# Power.net
KiCad netlist of a schematic drawn in Altium Designer
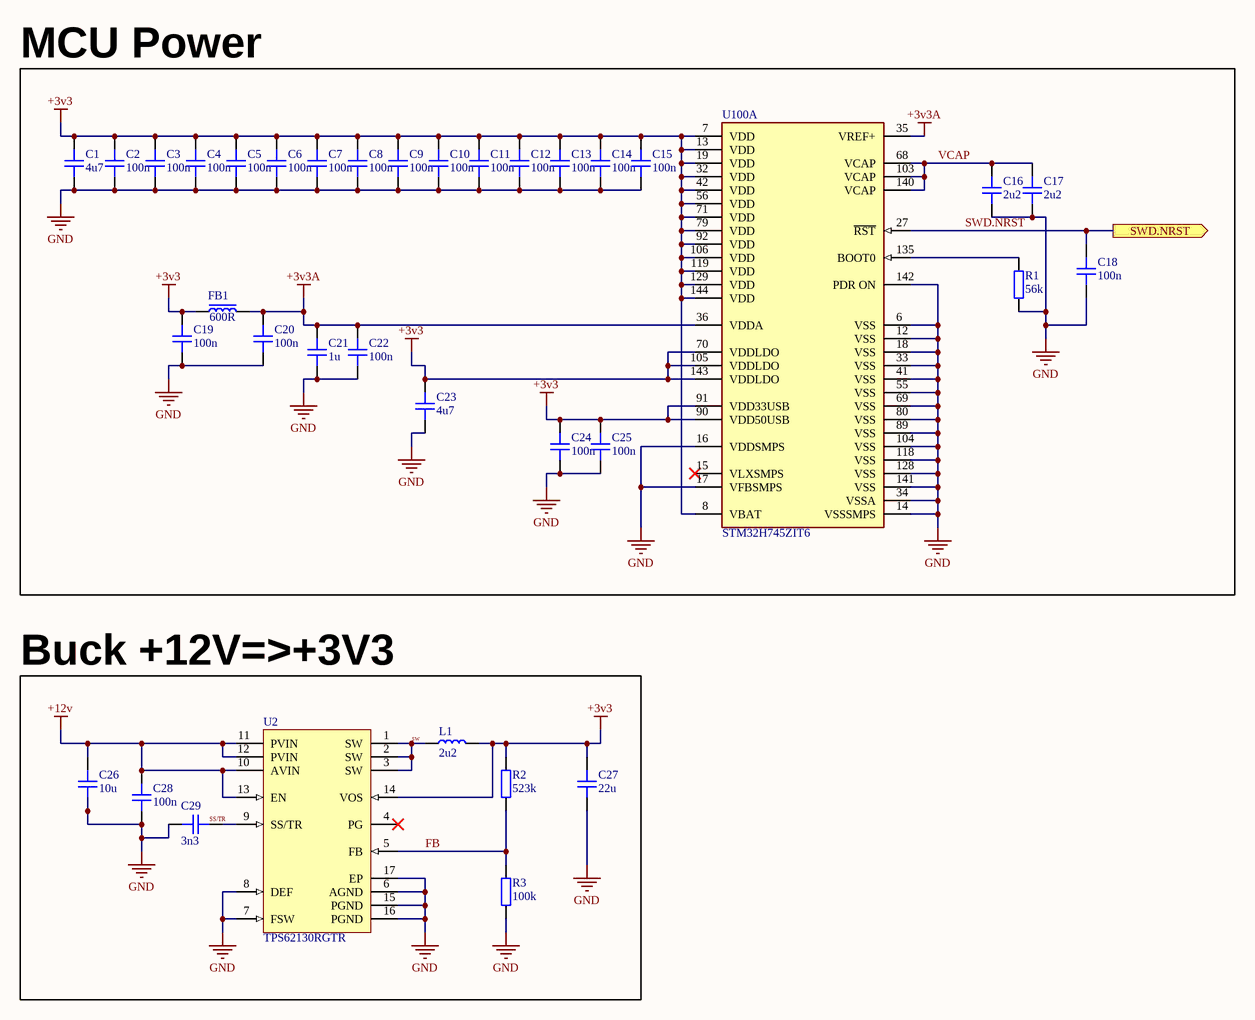
[diagram p0: Power.SchDoc]

(export (version "E")
  (design (tool "Eeschema 10.0.6"))
  (components
    (comp (ref "C1")
      (value "4u7")
      (footprint "CAP_0603")
      (description "Capacitor SMD 0603")
      (libsource (lib "Schematic-Lib-PhilsLab") (part "CAP_0603"))
    )
    (comp (ref "C2")
      (value "100n")
      (footprint "CAP_0402")
      (description "Capacitor SMD 0402")
      (libsource (lib "Schematic-Lib-PhilsLab") (part "CAP_0402"))
    )
    (comp (ref "C3")
      (value "100n")
      (footprint "CAP_0402")
      (description "Capacitor SMD 0402")
      (libsource (lib "Schematic-Lib-PhilsLab") (part "CAP_0402"))
    )
    (comp (ref "C4")
      (value "100n")
      (footprint "CAP_0402")
      (description "Capacitor SMD 0402")
      (libsource (lib "Schematic-Lib-PhilsLab") (part "CAP_0402"))
    )
    (comp (ref "C5")
      (value "100n")
      (footprint "CAP_0402")
      (description "Capacitor SMD 0402")
      (libsource (lib "Schematic-Lib-PhilsLab") (part "CAP_0402"))
    )
    (comp (ref "C6")
      (value "100n")
      (footprint "CAP_0402")
      (description "Capacitor SMD 0402")
      (libsource (lib "Schematic-Lib-PhilsLab") (part "CAP_0402"))
    )
    (comp (ref "C7")
      (value "100n")
      (footprint "CAP_0402")
      (description "Capacitor SMD 0402")
      (libsource (lib "Schematic-Lib-PhilsLab") (part "CAP_0402"))
    )
    (comp (ref "C8")
      (value "100n")
      (footprint "CAP_0402")
      (description "Capacitor SMD 0402")
      (libsource (lib "Schematic-Lib-PhilsLab") (part "CAP_0402"))
    )
    (comp (ref "C9")
      (value "100n")
      (footprint "CAP_0402")
      (description "Capacitor SMD 0402")
      (libsource (lib "Schematic-Lib-PhilsLab") (part "CAP_0402"))
    )
    (comp (ref "C10")
      (value "100n")
      (footprint "CAP_0402")
      (description "Capacitor SMD 0402")
      (libsource (lib "Schematic-Lib-PhilsLab") (part "CAP_0402"))
    )
    (comp (ref "C11")
      (value "100n")
      (footprint "CAP_0402")
      (description "Capacitor SMD 0402")
      (libsource (lib "Schematic-Lib-PhilsLab") (part "CAP_0402"))
    )
    (comp (ref "C12")
      (value "100n")
      (footprint "CAP_0402")
      (description "Capacitor SMD 0402")
      (libsource (lib "Schematic-Lib-PhilsLab") (part "CAP_0402"))
    )
    (comp (ref "C13")
      (value "100n")
      (footprint "CAP_0402")
      (description "Capacitor SMD 0402")
      (libsource (lib "Schematic-Lib-PhilsLab") (part "CAP_0402"))
    )
    (comp (ref "C14")
      (value "100n")
      (footprint "CAP_0402")
      (description "Capacitor SMD 0402")
      (libsource (lib "Schematic-Lib-PhilsLab") (part "CAP_0402"))
    )
    (comp (ref "C15")
      (value "100n")
      (footprint "CAP_0402")
      (description "Capacitor SMD 0402")
      (libsource (lib "Schematic-Lib-PhilsLab") (part "CAP_0402"))
    )
    (comp (ref "C16")
      (value "2u2")
      (footprint "CAP_0402")
      (description "Capacitor SMD 0402")
      (libsource (lib "Schematic-Lib-PhilsLab") (part "CAP_0402"))
    )
    (comp (ref "C17")
      (value "2u2")
      (footprint "CAP_0402")
      (description "Capacitor SMD 0402")
      (libsource (lib "Schematic-Lib-PhilsLab") (part "CAP_0402"))
    )
    (comp (ref "C18")
      (value "100n")
      (footprint "CAP_0402")
      (description "Capacitor SMD 0402")
      (libsource (lib "Schematic-Lib-PhilsLab") (part "CAP_0402"))
    )
    (comp (ref "C19")
      (value "100n")
      (footprint "CAP_0402")
      (description "Capacitor SMD 0402")
      (libsource (lib "Schematic-Lib-PhilsLab") (part "CAP_0402"))
    )
    (comp (ref "C20")
      (value "100n")
      (footprint "CAP_0402")
      (description "Capacitor SMD 0402")
      (libsource (lib "Schematic-Lib-PhilsLab") (part "CAP_0402"))
    )
    (comp (ref "C21")
      (value "1u")
      (footprint "CAP_0402")
      (description "Capacitor SMD 0402")
      (libsource (lib "Schematic-Lib-PhilsLab") (part "CAP_0402"))
    )
    (comp (ref "C22")
      (value "100n")
      (footprint "CAP_0402")
      (description "Capacitor SMD 0402")
      (libsource (lib "Schematic-Lib-PhilsLab") (part "CAP_0402"))
    )
    (comp (ref "C23")
      (value "4u7")
      (footprint "CAP_0603")
      (description "Capacitor SMD 0603")
      (libsource (lib "Schematic-Lib-PhilsLab") (part "CAP_0603"))
    )
    (comp (ref "C24")
      (value "100n")
      (footprint "CAP_0402")
      (description "Capacitor SMD 0402")
      (libsource (lib "Schematic-Lib-PhilsLab") (part "CAP_0402"))
    )
    (comp (ref "C25")
      (value "100n")
      (footprint "CAP_0402")
      (description "Capacitor SMD 0402")
      (libsource (lib "Schematic-Lib-PhilsLab") (part "CAP_0402"))
    )
    (comp (ref "C26")
      (value "10u")
      (footprint "CAP_0805")
      (description "Capacitor SMD 0805")
      (libsource (lib "Schematic-Lib-PhilsLab") (part "CAP_0805"))
    )
    (comp (ref "C27")
      (value "22u")
      (footprint "CAP_0805")
      (description "Capacitor SMD 0805")
      (libsource (lib "Schematic-Lib-PhilsLab") (part "CAP_0805"))
    )
    (comp (ref "C28")
      (value "100n")
      (footprint "CAP_0402")
      (description "Capacitor SMD 0402")
      (libsource (lib "Schematic-Lib-PhilsLab") (part "CAP_0402"))
    )
    (comp (ref "C29")
      (value "3n3")
      (footprint "CAP_0402")
      (description "Capacitor SMD 0402")
      (libsource (lib "Schematic-Lib-PhilsLab") (part "CAP_0402"))
    )
    (comp (ref "FB1")
      (value "600R")
      (footprint "FB_0603")
      (description "Ferrite Bead SMD 0603 2A 350mΩ 600Ω@100MHz ±25%")
      (libsource (lib "Schematic-Lib-PhilsLab") (part "FB_0603"))
    )
    (comp (ref "L1")
      (value "2u2")
      (footprint "IND_1008")
      (description "Inductor SMD 1008")
      (libsource (lib "Schematic-Lib-PhilsLab") (part "IND_1008"))
    )
    (comp (ref "R1")
      (value "56k")
      (footprint "RES_0402")
      (description "Resistor SMD 0402")
      (libsource (lib "Schematic-Lib-PhilsLab") (part "RES_0402"))
    )
    (comp (ref "R2")
      (value "523k")
      (footprint "RES_0402")
      (description "Resistor SMD 0402")
      (libsource (lib "Schematic-Lib-PhilsLab") (part "RES_0402"))
    )
    (comp (ref "R3")
      (value "100k")
      (footprint "RES_0402")
      (description "Resistor SMD 0402")
      (libsource (lib "Schematic-Lib-PhilsLab") (part "RES_0402"))
    )
    (comp (ref "U2")
      (value "TPS62130RGTR")
      (footprint "RGT0016C_V")
      (fields (field (name "MANUFACTURER") "Texas Instruments"))
      (libsource (lib "Altium Content Vault") (part "TI-TPS62130RGT16-1700X1700TP"))
    )
    (comp (ref "U100")
      (value "STM32H745ZIT6")
      (footprint "FP-LQFP144-1A-MFG")
      (description "HIGH-PERFORMANCE AND DSP WITH DP")
      (fields
        (field (name "OCTOPART") "https://octopart.com/stm32h745zit6-stmicroelectronics-100293939")
        (field (name "MANUFACTURER") "STMicroelectronics")
      )
      (libsource (lib "Altium Content Vault") (part "f5432ce9894f79c0085309acf87c031"))
    )
  )
  (nets
    (net (code "1") (name "+3v3") (class "Default")
      (node (ref "C1") (pin "2") (pinfunction "2_2") (pintype "passive"))
      (node (ref "C10") (pin "2") (pinfunction "2_2") (pintype "passive"))
      (node (ref "C11") (pin "2") (pinfunction "2_2") (pintype "passive"))
      (node (ref "C12") (pin "2") (pinfunction "2_2") (pintype "passive"))
      (node (ref "C13") (pin "2") (pinfunction "2_2") (pintype "passive"))
      (node (ref "C14") (pin "2") (pinfunction "2_2") (pintype "passive"))
      (node (ref "C15") (pin "2") (pinfunction "2_2") (pintype "passive"))
      (node (ref "C19") (pin "2") (pinfunction "2_2") (pintype "passive"))
      (node (ref "C2") (pin "2") (pinfunction "2_2") (pintype "passive"))
      (node (ref "C23") (pin "2") (pinfunction "2_2") (pintype "passive"))
      (node (ref "C24") (pin "2") (pinfunction "2_2") (pintype "passive"))
      (node (ref "C25") (pin "2") (pinfunction "2_2") (pintype "passive"))
      (node (ref "C27") (pin "2") (pinfunction "2_2") (pintype "passive"))
      (node (ref "C3") (pin "2") (pinfunction "2_2") (pintype "passive"))
      (node (ref "C4") (pin "2") (pinfunction "2_2") (pintype "passive"))
      (node (ref "C5") (pin "2") (pinfunction "2_2") (pintype "passive"))
      (node (ref "C6") (pin "2") (pinfunction "2_2") (pintype "passive"))
      (node (ref "C7") (pin "2") (pinfunction "2_2") (pintype "passive"))
      (node (ref "C8") (pin "2") (pinfunction "2_2") (pintype "passive"))
      (node (ref "C9") (pin "2") (pinfunction "2_2") (pintype "passive"))
      (node (ref "FB1") (pin "1") (pinfunction "1_1") (pintype "passive"))
      (node (ref "L1") (pin "2") (pinfunction "2_2") (pintype "passive"))
      (node (ref "R2") (pin "2") (pinfunction "2_2") (pintype "passive"))
      (node (ref "U100") (pin "105") (pinfunction "VDDLDO_105") (pintype "power_in"))
      (node (ref "U100") (pin "106") (pinfunction "VDD_106") (pintype "power_in"))
      (node (ref "U100") (pin "119") (pinfunction "VDD_119") (pintype "power_in"))
      (node (ref "U100") (pin "129") (pinfunction "VDD_129") (pintype "power_in"))
      (node (ref "U100") (pin "13") (pinfunction "VDD_13") (pintype "power_in"))
      (node (ref "U100") (pin "143") (pinfunction "VDDLDO_143") (pintype "power_in"))
      (node (ref "U100") (pin "144") (pinfunction "VDD_144") (pintype "power_in"))
      (node (ref "U100") (pin "19") (pinfunction "VDD_19") (pintype "power_in"))
      (node (ref "U100") (pin "32") (pinfunction "VDD_32") (pintype "power_in"))
      (node (ref "U100") (pin "42") (pinfunction "VDD_42") (pintype "power_in"))
      (node (ref "U100") (pin "56") (pinfunction "VDD_56") (pintype "power_in"))
      (node (ref "U100") (pin "7") (pinfunction "VDD_7") (pintype "power_in"))
      (node (ref "U100") (pin "70") (pinfunction "VDDLDO_70") (pintype "power_in"))
      (node (ref "U100") (pin "71") (pinfunction "VDD_71") (pintype "power_in"))
      (node (ref "U100") (pin "79") (pinfunction "VDD_79") (pintype "power_in"))
      (node (ref "U100") (pin "8") (pinfunction "VBAT_8") (pintype "power_in"))
      (node (ref "U100") (pin "90") (pinfunction "VDD50USB_90") (pintype "power_in"))
      (node (ref "U100") (pin "91") (pinfunction "VDD33USB_91") (pintype "power_in"))
      (node (ref "U100") (pin "92") (pinfunction "VDD_92") (pintype "power_in"))
      (node (ref "U2") (pin "14") (pinfunction "VOS_14") (pintype "input"))
    )
    (net (code "2") (name "+3v3A") (class "Default")
      (node (ref "C20") (pin "2") (pinfunction "2_2") (pintype "passive"))
      (node (ref "C21") (pin "2") (pinfunction "2_2") (pintype "passive"))
      (node (ref "C22") (pin "2") (pinfunction "2_2") (pintype "passive"))
      (node (ref "FB1") (pin "2") (pinfunction "2_2") (pintype "passive"))
      (node (ref "U100") (pin "35") (pinfunction "VREF+_35") (pintype "power_in"))
      (node (ref "U100") (pin "36") (pinfunction "VDDA_36") (pintype "power_in"))
    )
    (net (code "3") (name "+12v") (class "Default")
      (node (ref "C26") (pin "2") (pinfunction "2_2") (pintype "passive"))
      (node (ref "C28") (pin "2") (pinfunction "2_2") (pintype "passive"))
      (node (ref "U2") (pin "10") (pinfunction "AVIN_10") (pintype "power_in"))
      (node (ref "U2") (pin "11") (pinfunction "PVIN_11") (pintype "power_in"))
      (node (ref "U2") (pin "12") (pinfunction "PVIN_12") (pintype "power_in"))
      (node (ref "U2") (pin "13") (pinfunction "EN_13") (pintype "input"))
    )
    (net (code "4") (name "/FB") (class "Default")
      (node (ref "R2") (pin "1") (pinfunction "1_1") (pintype "passive"))
      (node (ref "R3") (pin "2") (pinfunction "2_2") (pintype "passive"))
      (node (ref "U2") (pin "5") (pinfunction "FB_5") (pintype "input"))
    )
    (net (code "6") (name "/SW") (class "Default")
      (node (ref "L1") (pin "1") (pinfunction "1_1") (pintype "passive"))
      (node (ref "U2") (pin "1") (pinfunction "SW_1") (pintype "power_in"))
      (node (ref "U2") (pin "2") (pinfunction "SW_2") (pintype "power_in"))
      (node (ref "U2") (pin "3") (pinfunction "SW_3") (pintype "power_in"))
    )
    (net (code "7") (name "/SWD.NRST") (class "Default")
      (node (ref "C18") (pin "2") (pinfunction "2_2") (pintype "passive"))
      (node (ref "U100") (pin "27") (pinfunction "~{RST}_27") (pintype "input"))
    )
    (net (code "8") (name "/VCAP") (class "Default")
      (node (ref "C16") (pin "2") (pinfunction "2_2") (pintype "passive"))
      (node (ref "C17") (pin "2") (pinfunction "2_2") (pintype "passive"))
      (node (ref "U100") (pin "103") (pinfunction "VCAP_103") (pintype "passive"))
      (node (ref "U100") (pin "140") (pinfunction "VCAP_140") (pintype "passive"))
      (node (ref "U100") (pin "68") (pinfunction "VCAP_68") (pintype "passive"))
    )
    (net (code "9") (name "GND") (class "Default")
      (node (ref "C1") (pin "1") (pinfunction "1_1") (pintype "passive"))
      (node (ref "C10") (pin "1") (pinfunction "1_1") (pintype "passive"))
      (node (ref "C11") (pin "1") (pinfunction "1_1") (pintype "passive"))
      (node (ref "C12") (pin "1") (pinfunction "1_1") (pintype "passive"))
      (node (ref "C13") (pin "1") (pinfunction "1_1") (pintype "passive"))
      (node (ref "C14") (pin "1") (pinfunction "1_1") (pintype "passive"))
      (node (ref "C15") (pin "1") (pinfunction "1_1") (pintype "passive"))
      (node (ref "C16") (pin "1") (pinfunction "1_1") (pintype "passive"))
      (node (ref "C17") (pin "1") (pinfunction "1_1") (pintype "passive"))
      (node (ref "C18") (pin "1") (pinfunction "1_1") (pintype "passive"))
      (node (ref "C19") (pin "1") (pinfunction "1_1") (pintype "passive"))
      (node (ref "C2") (pin "1") (pinfunction "1_1") (pintype "passive"))
      (node (ref "C20") (pin "1") (pinfunction "1_1") (pintype "passive"))
      (node (ref "C21") (pin "1") (pinfunction "1_1") (pintype "passive"))
      (node (ref "C22") (pin "1") (pinfunction "1_1") (pintype "passive"))
      (node (ref "C23") (pin "1") (pinfunction "1_1") (pintype "passive"))
      (node (ref "C24") (pin "1") (pinfunction "1_1") (pintype "passive"))
      (node (ref "C25") (pin "1") (pinfunction "1_1") (pintype "passive"))
      (node (ref "C26") (pin "1") (pinfunction "1_1") (pintype "passive"))
      (node (ref "C27") (pin "1") (pinfunction "1_1") (pintype "passive"))
      (node (ref "C28") (pin "1") (pinfunction "1_1") (pintype "passive"))
      (node (ref "C29") (pin "2") (pinfunction "2_2") (pintype "passive"))
      (node (ref "C3") (pin "1") (pinfunction "1_1") (pintype "passive"))
      (node (ref "C4") (pin "1") (pinfunction "1_1") (pintype "passive"))
      (node (ref "C5") (pin "1") (pinfunction "1_1") (pintype "passive"))
      (node (ref "C6") (pin "1") (pinfunction "1_1") (pintype "passive"))
      (node (ref "C7") (pin "1") (pinfunction "1_1") (pintype "passive"))
      (node (ref "C8") (pin "1") (pinfunction "1_1") (pintype "passive"))
      (node (ref "C9") (pin "1") (pinfunction "1_1") (pintype "passive"))
      (node (ref "R1") (pin "1") (pinfunction "1_1") (pintype "passive"))
      (node (ref "R3") (pin "1") (pinfunction "1_1") (pintype "passive"))
      (node (ref "U100") (pin "104") (pinfunction "VSS_104") (pintype "power_in"))
      (node (ref "U100") (pin "118") (pinfunction "VSS_118") (pintype "power_in"))
      (node (ref "U100") (pin "12") (pinfunction "VSS_12") (pintype "power_in"))
      (node (ref "U100") (pin "128") (pinfunction "VSS_128") (pintype "power_in"))
      (node (ref "U100") (pin "14") (pinfunction "VSSSMPS_14") (pintype "power_in"))
      (node (ref "U100") (pin "141") (pinfunction "VSS_141") (pintype "power_in"))
      (node (ref "U100") (pin "142") (pinfunction "PDR_ON_142") (pintype "passive"))
      (node (ref "U100") (pin "16") (pinfunction "VDDSMPS_16") (pintype "power_in"))
      (node (ref "U100") (pin "17") (pinfunction "VFBSMPS_17") (pintype "power_in"))
      (node (ref "U100") (pin "18") (pinfunction "VSS_18") (pintype "power_in"))
      (node (ref "U100") (pin "33") (pinfunction "VSS_33") (pintype "power_in"))
      (node (ref "U100") (pin "34") (pinfunction "VSSA_34") (pintype "power_in"))
      (node (ref "U100") (pin "41") (pinfunction "VSS_41") (pintype "power_in"))
      (node (ref "U100") (pin "55") (pinfunction "VSS_55") (pintype "power_in"))
      (node (ref "U100") (pin "6") (pinfunction "VSS_6") (pintype "power_in"))
      (node (ref "U100") (pin "69") (pinfunction "VSS_69") (pintype "power_in"))
      (node (ref "U100") (pin "80") (pinfunction "VSS_80") (pintype "power_in"))
      (node (ref "U100") (pin "89") (pinfunction "VSS_89") (pintype "power_in"))
      (node (ref "U2") (pin "15") (pinfunction "PGND_15") (pintype "power_in"))
      (node (ref "U2") (pin "16") (pinfunction "PGND_16") (pintype "power_in"))
      (node (ref "U2") (pin "17") (pinfunction "EP_17") (pintype "power_in"))
      (node (ref "U2") (pin "6") (pinfunction "AGND_6") (pintype "power_in"))
      (node (ref "U2") (pin "7") (pinfunction "FSW_7") (pintype "input"))
      (node (ref "U2") (pin "8") (pinfunction "DEF_8") (pintype "input"))
    )
    (net (code "10") (name "Net-(U2-SS{slash}TR)") (class "Default")
      (node (ref "C29") (pin "1") (pinfunction "1_1") (pintype "passive"))
      (node (ref "U2") (pin "9") (pinfunction "SS/TR_9") (pintype "input"))
    )
    (net (code "11") (name "Net-(U100A-BOOT0)") (class "Default")
      (node (ref "R1") (pin "2") (pinfunction "2_2") (pintype "passive"))
      (node (ref "U100") (pin "135") (pinfunction "BOOT0_135") (pintype "input"))
    )
    (net (code "12") (name "unconnected-(U2-PG-Pad4)") (class "Default")
      (node (ref "U2") (pin "4") (pinfunction "PG_4") (pintype "tri_state+no_connect"))
    )
    (net (code "13") (name "unconnected-(U100A-VLXSMPS-Pad15)") (class "Default")
      (node (ref "U100") (pin "15") (pinfunction "VLXSMPS_15") (pintype "power_in+no_connect"))
    )
  )
)
